# Super-Regenerative-VHF-2Transistor-RickA.net
KiCad netlist of a schematic drawn in EAGLE
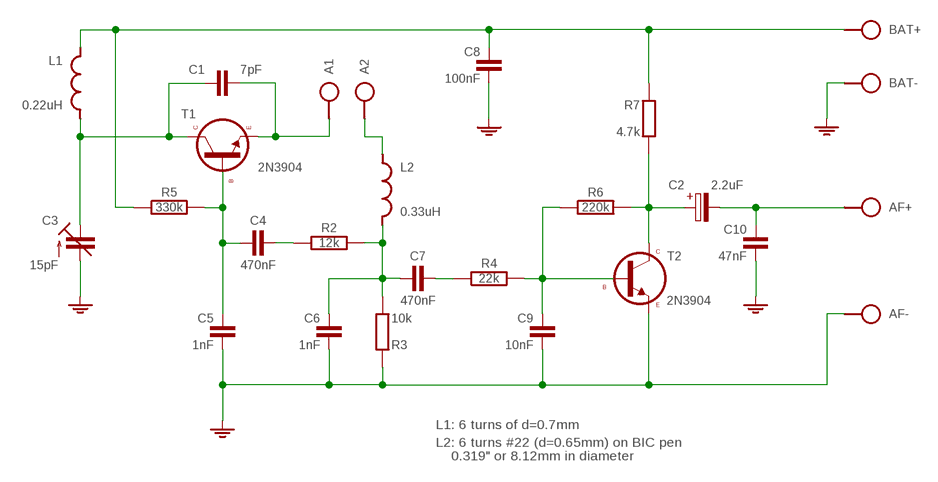
[diagram p0: schematic, sheet 1]

(export (version "E")
  (design (tool "Eeschema 10.0.6"))
  (components
    (comp (ref "A1")
      (value "SPAD")
      (footprint "eagle-import:SPAD")
      (libsource (lib "eagle-import") (part "SPAD"))
    )
    (comp (ref "A2")
      (value "SPAD")
      (footprint "eagle-import:SPAD")
      (libsource (lib "eagle-import") (part "SPAD"))
    )
    (comp (ref "AF+")
      (value "SPAD")
      (footprint "eagle-import:SPAD")
      (libsource (lib "eagle-import") (part "SPAD"))
    )
    (comp (ref "AF-")
      (value "SPAD")
      (footprint "eagle-import:SPAD")
      (libsource (lib "eagle-import") (part "SPAD"))
    )
    (comp (ref "BAT+")
      (value "SPAD")
      (footprint "eagle-import:SPAD")
      (libsource (lib "eagle-import") (part "SPAD"))
    )
    (comp (ref "BAT-")
      (value "SPAD")
      (footprint "eagle-import:SPAD")
      (libsource (lib "eagle-import") (part "SPAD"))
    )
    (comp (ref "C1")
      (value "7pF")
      (footprint "eagle-import:C050-020X036")
      (libsource (lib "eagle-import") (part "C050-020X036"))
    )
    (comp (ref "C2")
      (value "2.2uF")
      (footprint "eagle-import:E2,5-3")
      (libsource (lib "eagle-import") (part "CPOLE2,5-3"))
    )
    (comp (ref "C3")
      (value "15pF")
      (footprint "eagle-import:TRIM-2222-808")
      (libsource (lib "eagle-import") (part "C-TR-PH201272222-808-2PINB"))
    )
    (comp (ref "C4")
      (value "470nF")
      (footprint "eagle-import:C050-024X044_V")
      (libsource (lib "eagle-import") (part "C050-024X044/V"))
    )
    (comp (ref "C5")
      (value "1nF")
      (footprint "eagle-import:C025-020X036")
      (libsource (lib "eagle-import") (part "C025-020X036"))
    )
    (comp (ref "C6")
      (value "1nF")
      (footprint "eagle-import:C025-020X036")
      (libsource (lib "eagle-import") (part "C025-020X036"))
    )
    (comp (ref "C7")
      (value "470nF")
      (footprint "eagle-import:C050-024X044_V")
      (libsource (lib "eagle-import") (part "C050-024X044/V"))
    )
    (comp (ref "C8")
      (value "100nF")
      (footprint "eagle-import:C050-020X044")
      (libsource (lib "eagle-import") (part "C050-020X044"))
    )
    (comp (ref "C9")
      (value "10nF")
      (footprint "eagle-import:C025-015X024")
      (libsource (lib "eagle-import") (part "C025-015X024"))
    )
    (comp (ref "C10")
      (value "47nF")
      (footprint "eagle-import:C050-020X036_V")
      (libsource (lib "eagle-import") (part "C050-020X036/V"))
    )
    (comp (ref "L1")
      (value "0.22uH")
      (footprint "eagle-import:L-04-5_6V")
      (libsource (lib "eagle-import") (part "L-SHORT04-5/5V"))
    )
    (comp (ref "L2")
      (value "0.33uH")
      (footprint "eagle-import:L-08-5_8")
      (libsource (lib "eagle-import") (part "L-SHORTL-08-5/8"))
    )
    (comp (ref "R2")
      (value "12k")
      (footprint "eagle-import:0202_7")
      (libsource (lib "eagle-import") (part "R-H0202/7"))
    )
    (comp (ref "R3")
      (value "10k")
      (footprint "eagle-import:0202_5-V")
      (libsource (lib "eagle-import") (part "R0202/5-V"))
    )
    (comp (ref "R4")
      (value "22k")
      (footprint "eagle-import:0202_7-V")
      (libsource (lib "eagle-import") (part "R-H0202/7-V"))
    )
    (comp (ref "R5")
      (value "330k")
      (footprint "eagle-import:0202_7")
      (libsource (lib "eagle-import") (part "R-H0202/7"))
    )
    (comp (ref "R6")
      (value "220k")
      (footprint "eagle-import:0202_7-V")
      (libsource (lib "eagle-import") (part "R-H0202/7-V"))
    )
    (comp (ref "R7")
      (value "4.7k")
      (footprint "eagle-import:0202_7-V")
      (libsource (lib "eagle-import") (part "R0202/7-V"))
    )
    (comp (ref "T1")
      (value "2N3904")
      (footprint "eagle-import:TO92")
      (libsource (lib "eagle-import") (part "2N3904"))
    )
    (comp (ref "T2")
      (value "2N3904")
      (footprint "eagle-import:TO92")
      (libsource (lib "eagle-import") (part "2N3904"))
    )
  )
  (nets
    (net (code "1") (name "GND") (class "Default")
      (node (ref "AF-") (pin "1") (pinfunction "P$1_1") (pintype "passive"))
      (node (ref "BAT-") (pin "1") (pinfunction "P$1_1") (pintype "passive"))
      (node (ref "C10") (pin "2") (pinfunction "2_2") (pintype "passive"))
      (node (ref "C3") (pin "2") (pinfunction "A_2") (pintype "passive"))
      (node (ref "C5") (pin "2") (pinfunction "2_2") (pintype "passive"))
      (node (ref "C6") (pin "2") (pinfunction "2_2") (pintype "passive"))
      (node (ref "C8") (pin "2") (pinfunction "2_2") (pintype "passive"))
      (node (ref "C9") (pin "2") (pinfunction "2_2") (pintype "passive"))
      (node (ref "R3") (pin "1") (pinfunction "2_1") (pintype "passive"))
      (node (ref "T2") (pin "1") (pinfunction "E_1") (pintype "passive"))
    )
    (net (code "2") (name "Net-(A1-P$1)") (class "Default")
      (node (ref "A1") (pin "1") (pinfunction "P$1_1") (pintype "passive"))
      (node (ref "C1") (pin "1") (pinfunction "1_1") (pintype "passive"))
      (node (ref "T1") (pin "1") (pinfunction "E_1") (pintype "passive"))
    )
    (net (code "3") (name "Net-(A2-P$1)") (class "Default")
      (node (ref "A2") (pin "1") (pinfunction "P$1_1") (pintype "passive"))
      (node (ref "L2") (pin "2") (pinfunction "2_2") (pintype "passive"))
    )
    (net (code "4") (name "Net-(AF+-P$1)") (class "Default")
      (node (ref "AF+") (pin "1") (pinfunction "P$1_1") (pintype "passive"))
      (node (ref "C10") (pin "1") (pinfunction "1_1") (pintype "passive"))
      (node (ref "C2") (pin "-") (pinfunction "-_-") (pintype "passive"))
    )
    (net (code "5") (name "Net-(BAT+-P$1)") (class "Default")
      (node (ref "BAT+") (pin "1") (pinfunction "P$1_1") (pintype "passive"))
      (node (ref "C8") (pin "1") (pinfunction "1_1") (pintype "passive"))
      (node (ref "L1") (pin "1") (pinfunction "2_1") (pintype "passive"))
      (node (ref "R5") (pin "1") (pinfunction "1_1") (pintype "passive"))
      (node (ref "R7") (pin "1") (pinfunction "2_1") (pintype "passive"))
    )
    (net (code "6") (name "Net-(C3-E)") (class "Default")
      (node (ref "C1") (pin "2") (pinfunction "2_2") (pintype "passive"))
      (node (ref "C3") (pin "3") (pinfunction "E_3") (pintype "passive"))
      (node (ref "L1") (pin "2") (pinfunction "1_2") (pintype "passive"))
      (node (ref "T1") (pin "3") (pinfunction "C_3") (pintype "passive"))
    )
    (net (code "7") (name "Net-(C4-Pad1)") (class "Default")
      (node (ref "C4") (pin "1") (pinfunction "1_1") (pintype "passive"))
      (node (ref "R2") (pin "1") (pinfunction "1_1") (pintype "passive"))
    )
    (net (code "8") (name "Net-(C7-Pad1)") (class "Default")
      (node (ref "C7") (pin "1") (pinfunction "1_1") (pintype "passive"))
      (node (ref "R4") (pin "1") (pinfunction "1_1") (pintype "passive"))
    )
    (net (code "9") (name "Net-(R3-1)") (class "Default")
      (node (ref "C6") (pin "1") (pinfunction "1_1") (pintype "passive"))
      (node (ref "C7") (pin "2") (pinfunction "2_2") (pintype "passive"))
      (node (ref "L2") (pin "1") (pinfunction "1_1") (pintype "passive"))
      (node (ref "R2") (pin "2") (pinfunction "2_2") (pintype "passive"))
      (node (ref "R3") (pin "2") (pinfunction "1_2") (pintype "passive"))
    )
    (net (code "10") (name "Net-(R7-1)") (class "Default")
      (node (ref "C2") (pin "+") (pinfunction "+_+") (pintype "passive"))
      (node (ref "R6") (pin "2") (pinfunction "2_2") (pintype "passive"))
      (node (ref "R7") (pin "2") (pinfunction "1_2") (pintype "passive"))
      (node (ref "T2") (pin "3") (pinfunction "C_3") (pintype "passive"))
    )
    (net (code "11") (name "Net-(T1-B)") (class "Default")
      (node (ref "C4") (pin "2") (pinfunction "2_2") (pintype "passive"))
      (node (ref "C5") (pin "1") (pinfunction "1_1") (pintype "passive"))
      (node (ref "R5") (pin "2") (pinfunction "2_2") (pintype "passive"))
      (node (ref "T1") (pin "2") (pinfunction "B_2") (pintype "passive"))
    )
    (net (code "12") (name "Net-(T2-B)") (class "Default")
      (node (ref "C9") (pin "1") (pinfunction "1_1") (pintype "passive"))
      (node (ref "R4") (pin "2") (pinfunction "2_2") (pintype "passive"))
      (node (ref "R6") (pin "1") (pinfunction "1_1") (pintype "passive"))
      (node (ref "T2") (pin "2") (pinfunction "B_2") (pintype "passive"))
    )
  )
)
